# smiw-proj.net
KiCad netlist of a schematic drawn in EAGLE
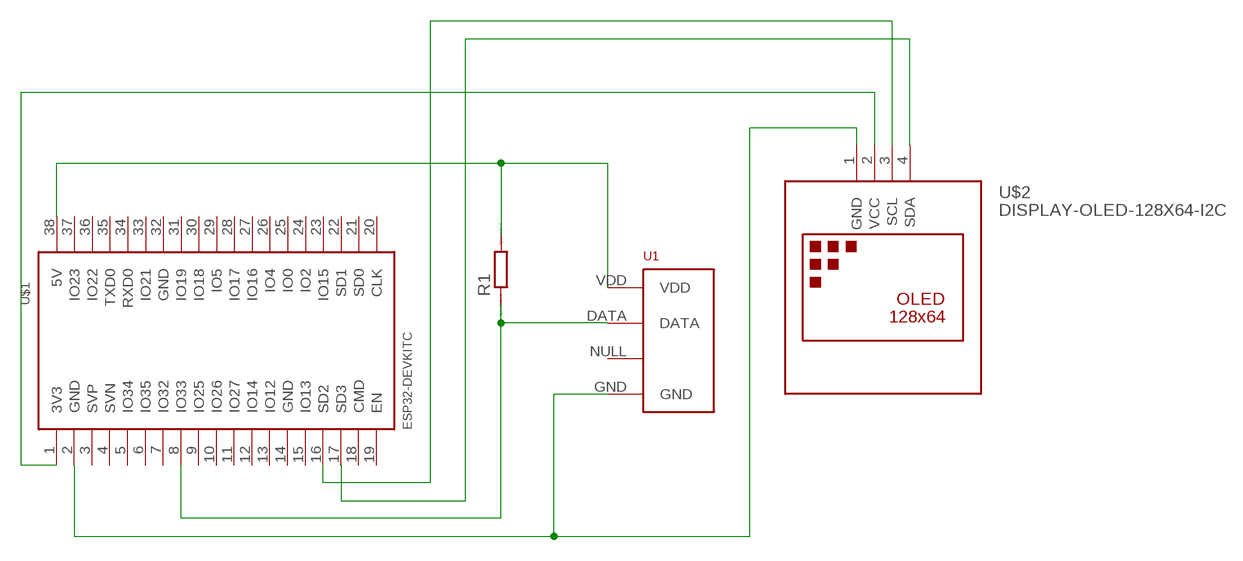
[diagram p0: schematic, sheet 1]

(export (version "E")
  (design (tool "Eeschema 10.0.6"))
  (components
    (comp (ref "R1")
      (value "R0204/7")
      (footprint "eagle-import:0204_7")
      (libsource (lib "eagle-import") (part "R0204/7"))
    )
    (comp (ref "U$1")
      (value "ESP32DEVKITC")
      (footprint "eagle-import:ESP32-DEVKITC")
      (fields (field (name "MF") "Espressif Systems") (field (name "MP") "ESP32-DEVKITC"))
      (libsource (lib "eagle-import") (part "ESP32DEVKITC"))
    )
    (comp (ref "U$2")
      (value "DISPLAY-OLED-128X64-I2C")
      (footprint "eagle-import:DISPLAY-OLED-128X64-I2C")
      (libsource (lib "eagle-import") (part "DISPLAY-OLED-128X64-I2C"))
    )
    (comp (ref "U1")
      (value "RHT03_DHT-22_AM2302RA")
      (footprint "eagle-import:RHT03_DHT-22_RA")
      (libsource (lib "eagle-import") (part "RHT03_DHT-22_AM2302RA"))
    )
  )
  (nets
    (net (code "1") (name "Net-(U$1-3V3)") (class "Default")
      (node (ref "U$1") (pin "1") (pinfunction "3V3_1") (pintype "bidirectional"))
      (node (ref "U$2") (pin "2") (pinfunction "VCC_2") (pintype "power_in"))
    )
    (net (code "2") (name "Net-(U$1-5V)") (class "Default")
      (node (ref "R1") (pin "2") (pinfunction "2_2") (pintype "passive"))
      (node (ref "U$1") (pin "38") (pinfunction "5V_38") (pintype "bidirectional"))
      (node (ref "U1") (pin "VDD") (pinfunction "VDD_VDD") (pintype "power_in"))
    )
    (net (code "3") (name "Net-(U$1-IO33)") (class "Default")
      (node (ref "R1") (pin "1") (pinfunction "1_1") (pintype "passive"))
      (node (ref "U$1") (pin "8") (pinfunction "IO33_8") (pintype "bidirectional"))
      (node (ref "U1") (pin "DATA") (pinfunction "DATA_DATA") (pintype "bidirectional"))
    )
    (net (code "4") (name "Net-(U$1-SD2)") (class "Default")
      (node (ref "U$1") (pin "16") (pinfunction "SD2_16") (pintype "bidirectional"))
      (node (ref "U$2") (pin "3") (pinfunction "SCL_3") (pintype "bidirectional"))
    )
    (net (code "5") (name "Net-(U$1-SD3)") (class "Default")
      (node (ref "U$1") (pin "17") (pinfunction "SD3_17") (pintype "bidirectional"))
      (node (ref "U$2") (pin "4") (pinfunction "SDA_4") (pintype "bidirectional"))
    )
    (net (code "6") (name "Net-(U$2-GND)") (class "Default")
      (node (ref "U$1") (pin "2") (pinfunction "GND_2") (pintype "bidirectional"))
      (node (ref "U$2") (pin "1") (pinfunction "GND_1") (pintype "power_in"))
      (node (ref "U1") (pin "GND") (pinfunction "GND_GND") (pintype "power_in"))
    )
    (net (code "7") (name "unconnected-(U$1-CLK-Pad20)") (class "Default")
      (node (ref "U$1") (pin "20") (pinfunction "CLK_20") (pintype "bidirectional"))
    )
    (net (code "8") (name "unconnected-(U$1-CMD-Pad18)") (class "Default")
      (node (ref "U$1") (pin "18") (pinfunction "CMD_18") (pintype "bidirectional"))
    )
    (net (code "9") (name "unconnected-(U$1-EN-Pad19)") (class "Default")
      (node (ref "U$1") (pin "19") (pinfunction "EN_19") (pintype "bidirectional"))
    )
    (net (code "10") (name "unconnected-(U$1-GND-Pad14)") (class "Default")
      (node (ref "U$1") (pin "14") (pinfunction "GND_14") (pintype "bidirectional"))
    )
    (net (code "11") (name "unconnected-(U$1-GND-Pad32)") (class "Default")
      (node (ref "U$1") (pin "32") (pinfunction "GND_32") (pintype "bidirectional"))
    )
    (net (code "12") (name "unconnected-(U$1-IO0-Pad25)") (class "Default")
      (node (ref "U$1") (pin "25") (pinfunction "IO0_25") (pintype "bidirectional"))
    )
    (net (code "13") (name "unconnected-(U$1-IO2-Pad24)") (class "Default")
      (node (ref "U$1") (pin "24") (pinfunction "IO2_24") (pintype "bidirectional"))
    )
    (net (code "14") (name "unconnected-(U$1-IO4-Pad26)") (class "Default")
      (node (ref "U$1") (pin "26") (pinfunction "IO4_26") (pintype "bidirectional"))
    )
    (net (code "15") (name "unconnected-(U$1-IO5-Pad29)") (class "Default")
      (node (ref "U$1") (pin "29") (pinfunction "IO5_29") (pintype "bidirectional"))
    )
    (net (code "16") (name "unconnected-(U$1-IO12-Pad13)") (class "Default")
      (node (ref "U$1") (pin "13") (pinfunction "IO12_13") (pintype "bidirectional"))
    )
    (net (code "17") (name "unconnected-(U$1-IO13-Pad15)") (class "Default")
      (node (ref "U$1") (pin "15") (pinfunction "IO13_15") (pintype "bidirectional"))
    )
    (net (code "18") (name "unconnected-(U$1-IO14-Pad12)") (class "Default")
      (node (ref "U$1") (pin "12") (pinfunction "IO14_12") (pintype "bidirectional"))
    )
    (net (code "19") (name "unconnected-(U$1-IO15-Pad23)") (class "Default")
      (node (ref "U$1") (pin "23") (pinfunction "IO15_23") (pintype "bidirectional"))
    )
    (net (code "20") (name "unconnected-(U$1-IO16-Pad27)") (class "Default")
      (node (ref "U$1") (pin "27") (pinfunction "IO16_27") (pintype "bidirectional"))
    )
    (net (code "21") (name "unconnected-(U$1-IO17-Pad28)") (class "Default")
      (node (ref "U$1") (pin "28") (pinfunction "IO17_28") (pintype "bidirectional"))
    )
    (net (code "22") (name "unconnected-(U$1-IO18-Pad30)") (class "Default")
      (node (ref "U$1") (pin "30") (pinfunction "IO18_30") (pintype "bidirectional"))
    )
    (net (code "23") (name "unconnected-(U$1-IO19-Pad31)") (class "Default")
      (node (ref "U$1") (pin "31") (pinfunction "IO19_31") (pintype "bidirectional"))
    )
    (net (code "24") (name "unconnected-(U$1-IO21-Pad33)") (class "Default")
      (node (ref "U$1") (pin "33") (pinfunction "IO21_33") (pintype "bidirectional"))
    )
    (net (code "25") (name "unconnected-(U$1-IO22-Pad36)") (class "Default")
      (node (ref "U$1") (pin "36") (pinfunction "IO22_36") (pintype "bidirectional"))
    )
    (net (code "26") (name "unconnected-(U$1-IO23-Pad37)") (class "Default")
      (node (ref "U$1") (pin "37") (pinfunction "IO23_37") (pintype "bidirectional"))
    )
    (net (code "27") (name "unconnected-(U$1-IO25-Pad9)") (class "Default")
      (node (ref "U$1") (pin "9") (pinfunction "IO25_9") (pintype "bidirectional"))
    )
    (net (code "28") (name "unconnected-(U$1-IO26-Pad10)") (class "Default")
      (node (ref "U$1") (pin "10") (pinfunction "IO26_10") (pintype "bidirectional"))
    )
    (net (code "29") (name "unconnected-(U$1-IO27-Pad11)") (class "Default")
      (node (ref "U$1") (pin "11") (pinfunction "IO27_11") (pintype "bidirectional"))
    )
    (net (code "30") (name "unconnected-(U$1-IO32-Pad7)") (class "Default")
      (node (ref "U$1") (pin "7") (pinfunction "IO32_7") (pintype "bidirectional"))
    )
    (net (code "31") (name "unconnected-(U$1-IO34-Pad5)") (class "Default")
      (node (ref "U$1") (pin "5") (pinfunction "IO34_5") (pintype "bidirectional"))
    )
    (net (code "32") (name "unconnected-(U$1-IO35-Pad6)") (class "Default")
      (node (ref "U$1") (pin "6") (pinfunction "IO35_6") (pintype "bidirectional"))
    )
    (net (code "33") (name "unconnected-(U$1-RXD0-Pad34)") (class "Default")
      (node (ref "U$1") (pin "34") (pinfunction "RXD0_34") (pintype "bidirectional"))
    )
    (net (code "34") (name "unconnected-(U$1-SD0-Pad21)") (class "Default")
      (node (ref "U$1") (pin "21") (pinfunction "SD0_21") (pintype "bidirectional"))
    )
    (net (code "35") (name "unconnected-(U$1-SD1-Pad22)") (class "Default")
      (node (ref "U$1") (pin "22") (pinfunction "SD1_22") (pintype "bidirectional"))
    )
    (net (code "36") (name "unconnected-(U$1-SVN-Pad4)") (class "Default")
      (node (ref "U$1") (pin "4") (pinfunction "SVN_4") (pintype "bidirectional"))
    )
    (net (code "37") (name "unconnected-(U$1-SVP-Pad3)") (class "Default")
      (node (ref "U$1") (pin "3") (pinfunction "SVP_3") (pintype "bidirectional"))
    )
    (net (code "38") (name "unconnected-(U$1-TXD0-Pad35)") (class "Default")
      (node (ref "U$1") (pin "35") (pinfunction "TXD0_35") (pintype "bidirectional"))
    )
    (net (code "39") (name "unconnected-(U1-PadNULL)") (class "Default")
      (node (ref "U1") (pin "NULL") (pinfunction "NULL_NULL") (pintype "no_connect"))
    )
  )
)
